# SparkFun_GP-2106_Breakout.net
KiCad netlist of a schematic drawn in EAGLE
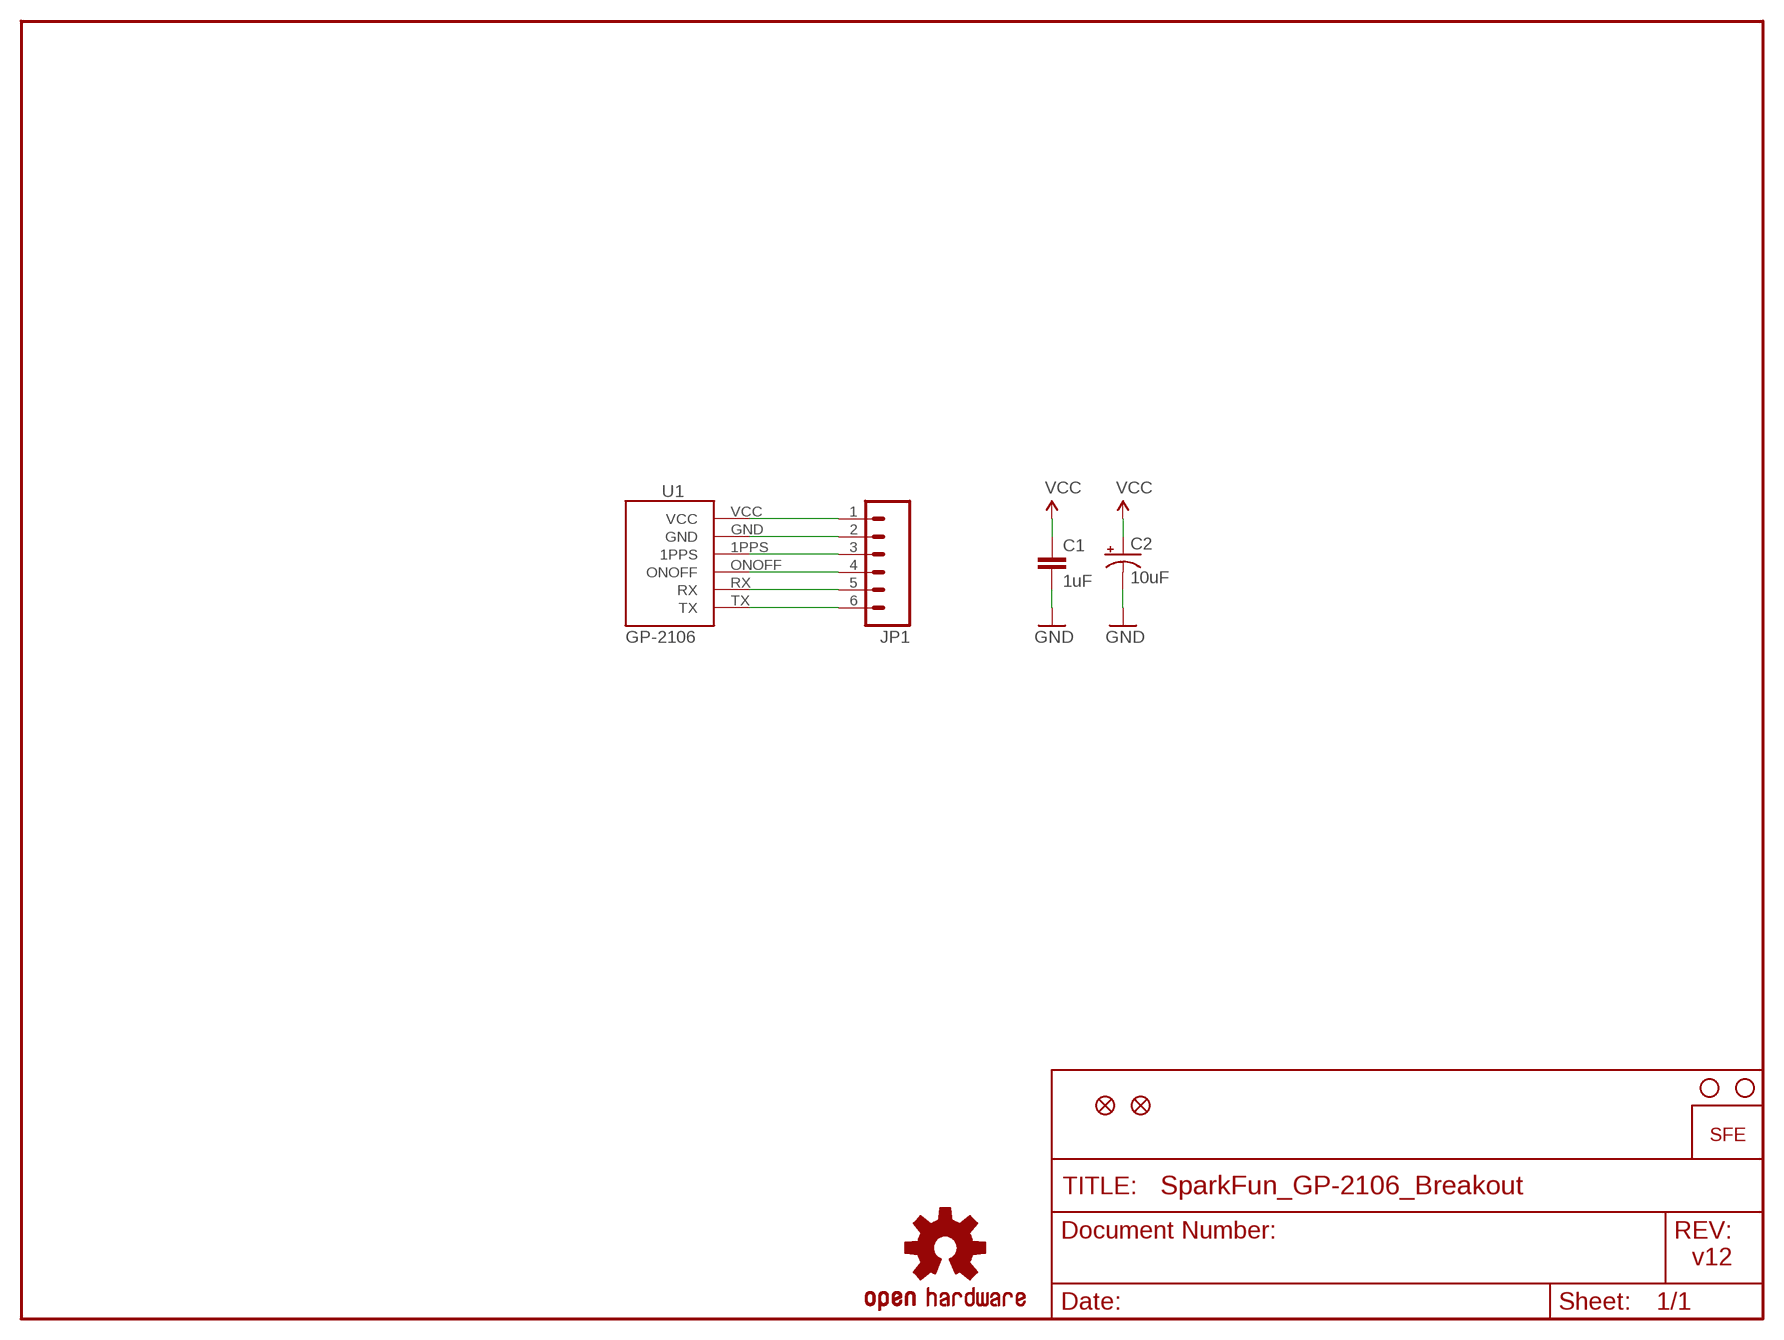
[diagram p0: schematic, sheet 1]

(export (version "E")
  (design (tool "Eeschema 10.0.6"))
  (components
    (comp (ref "C1")
      (value "1uF")
      (footprint "eagle-import:0402-CAP")
      (libsource (lib "eagle-import") (part "CAP0402-CAP"))
    )
    (comp (ref "C2")
      (value "10uF")
      (footprint "eagle-import:EIA3216")
      (libsource (lib "eagle-import") (part "CAP_POL1206"))
    )
    (comp (ref "JP1")
      (value "M06SIP")
      (footprint "eagle-import:1X06")
      (libsource (lib "eagle-import") (part "M06SIP"))
    )
    (comp (ref "JP2")
      (value "STAND-OFF")
      (footprint "eagle-import:STAND-OFF")
      (libsource (lib "eagle-import") (part "STAND-OFF"))
    )
    (comp (ref "JP3")
      (value "STAND-OFF")
      (footprint "eagle-import:STAND-OFF")
      (libsource (lib "eagle-import") (part "STAND-OFF"))
    )
    (comp (ref "JP4")
      (value "LOGO-SFESK")
      (footprint "eagle-import:SFE-LOGO-FLAME")
      (libsource (lib "eagle-import") (part "LOGO-SFESK"))
    )
    (comp (ref "JP5")
      (value "FIDUCIALUFIDUCIAL")
      (footprint "eagle-import:MICRO-FIDUCIAL")
      (libsource (lib "eagle-import") (part "FIDUCIALUFIDUCIAL"))
    )
    (comp (ref "JP6")
      (value "FIDUCIALUFIDUCIAL")
      (footprint "eagle-import:MICRO-FIDUCIAL")
      (libsource (lib "eagle-import") (part "FIDUCIALUFIDUCIAL"))
    )
    (comp (ref "U$1")
      (value "OSHW-LOGOS")
      (footprint "eagle-import:OSHW-LOGO-S")
      (libsource (lib "eagle-import") (part "OSHW-LOGOS"))
    )
    (comp (ref "U1")
      (value "GP-2106")
      (footprint "eagle-import:GP-2106")
      (libsource (lib "eagle-import") (part "GP-2106"))
    )
  )
  (nets
    (net (code "1") (name "GND") (class "Default")
      (node (ref "C1") (pin "2") (pinfunction "2_2") (pintype "passive"))
      (node (ref "C2") (pin "C") (pinfunction "-_C") (pintype "passive"))
      (node (ref "JP1") (pin "2") (pinfunction "2_2") (pintype "passive"))
      (node (ref "U1") (pin "GND") (pinfunction "GND_GND") (pintype "bidirectional"))
    )
    (net (code "2") (name "Net-(JP1-Pad3)") (class "Default")
      (node (ref "JP1") (pin "3") (pinfunction "3_3") (pintype "passive"))
      (node (ref "U1") (pin "1PPS") (pinfunction "1PPS_1PPS") (pintype "bidirectional"))
    )
    (net (code "3") (name "Net-(JP1-Pad4)") (class "Default")
      (node (ref "JP1") (pin "4") (pinfunction "4_4") (pintype "passive"))
      (node (ref "U1") (pin "ONOFF") (pinfunction "ONOFF_ONOFF") (pintype "bidirectional"))
    )
    (net (code "4") (name "Net-(JP1-Pad5)") (class "Default")
      (node (ref "JP1") (pin "5") (pinfunction "5_5") (pintype "passive"))
      (node (ref "U1") (pin "RX") (pinfunction "RX_RX") (pintype "bidirectional"))
    )
    (net (code "5") (name "Net-(JP1-Pad6)") (class "Default")
      (node (ref "JP1") (pin "6") (pinfunction "6_6") (pintype "passive"))
      (node (ref "U1") (pin "TX") (pinfunction "TX_TX") (pintype "bidirectional"))
    )
    (net (code "6") (name "VCC") (class "Default")
      (node (ref "C1") (pin "1") (pinfunction "1_1") (pintype "passive"))
      (node (ref "C2") (pin "A") (pinfunction "+_A") (pintype "passive"))
      (node (ref "JP1") (pin "1") (pinfunction "1_1") (pintype "passive"))
      (node (ref "U1") (pin "VCC") (pinfunction "VCC_VCC") (pintype "bidirectional"))
    )
  )
)
